# apu.net
KiCad netlist of a schematic drawn in Altium Designer
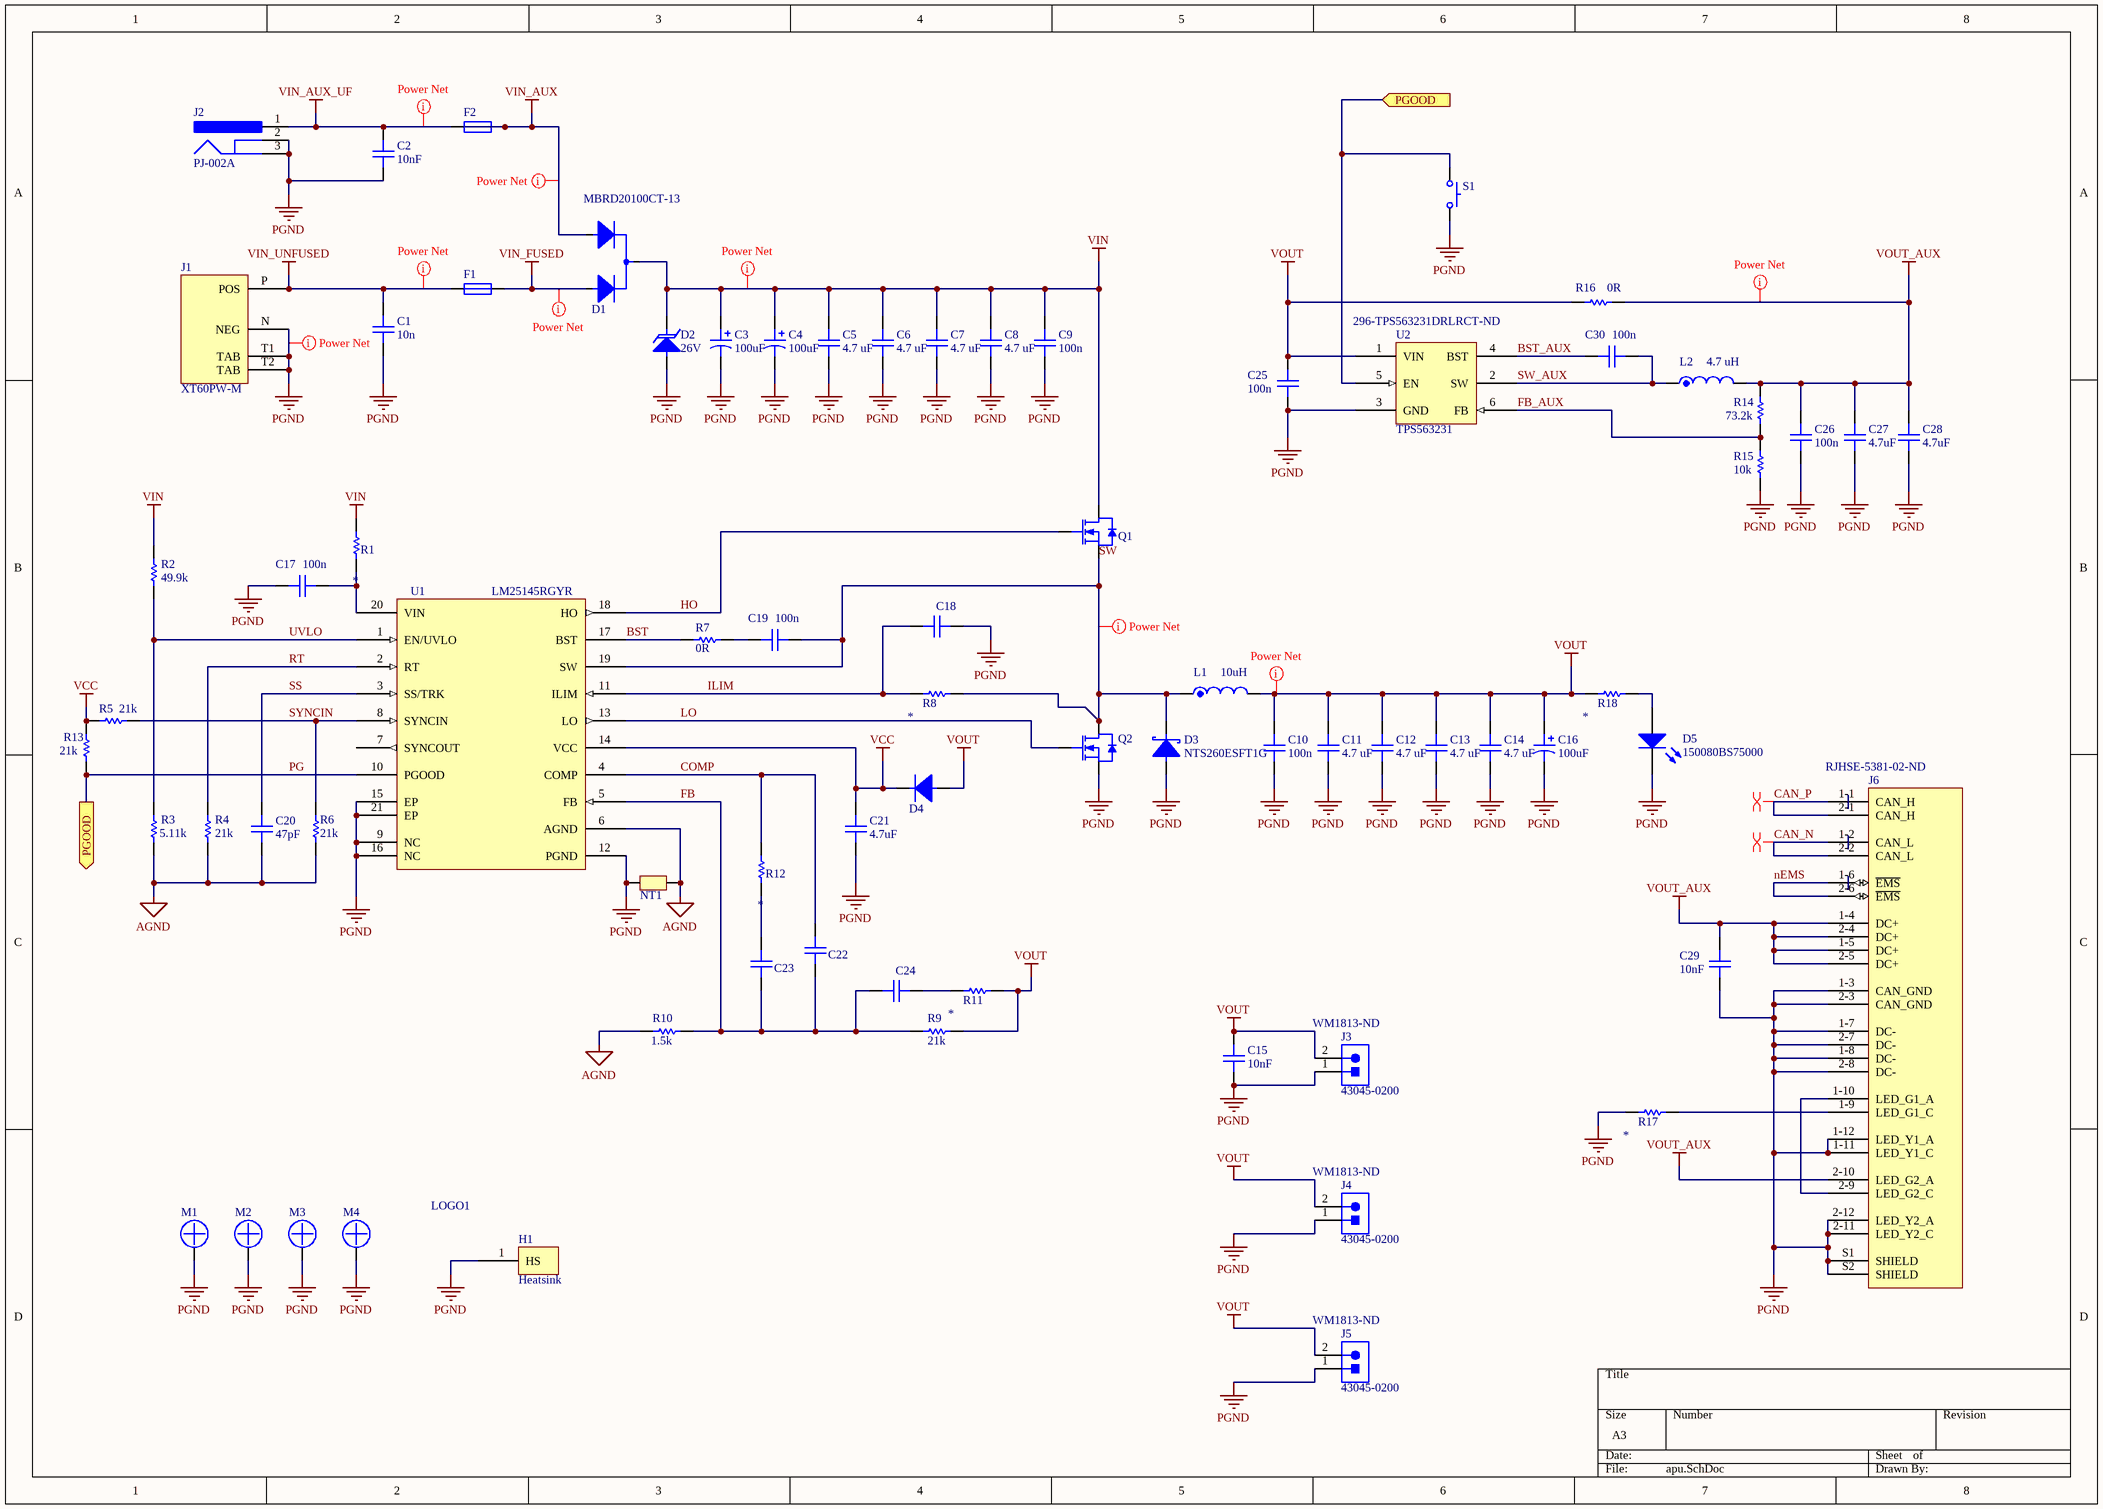
[diagram p0: apu.SchDoc]

(export (version "E")
  (design (tool "Eeschema 10.0.6"))
  (components
    (comp (ref "C1")
      (value "C")
      (footprint "C0603N")
      (description "CAP CER, 0.01UF, 50V, X7R, +/-20%, 0603")
      (fields (field (name "CAPACITANCE") "10n") (field (name "VOLTAGE") "50V"))
      (libsource (lib "libysk") (part "C"))
    )
    (comp (ref "C2")
      (value "C")
      (footprint "C0603N")
      (description "CAP CER, 0.01UF, 50V, X7R, +/-20%, 0603")
      (fields (field (name "CAPACITANCE") "10nF") (field (name "VOLTAGE") "50V"))
      (libsource (lib "libysk") (part "C"))
    )
    (comp (ref "C3")
      (value "UHE1H101MPD")
      (footprint "CPOL_8x11_5_THRU")
      (description "CAP ALUM 100UF 20% 50V RADIAL")
      (fields
        (field (name "CAPACITANCE") "100uF")
        (field (name "TOLERANCE") "20%")
        (field (name "VOLTAGE") "50V")
      )
      (libsource (lib "libysk") (part "CPOL"))
    )
    (comp (ref "C4")
      (value "UHE1H101MPD")
      (footprint "CPOL_8x11_5_THRU")
      (description "CAP ALUM 100UF 20% 50V RADIAL")
      (fields
        (field (name "CAPACITANCE") "100uF")
        (field (name "TOLERANCE") "20%")
        (field (name "VOLTAGE") "50V")
      )
      (libsource (lib "libysk") (part "CPOL"))
    )
    (comp (ref "C5")
      (value "UMK325B7475MM-P")
      (footprint "C1210N")
      (description "CAP CER 4.7UF 50V X7R 1210")
      (fields (field (name "CAPACITANCE") "4.7 uF") (field (name "VOLTAGE") "50 V"))
      (libsource (lib "libysk") (part "C"))
    )
    (comp (ref "C6")
      (value "UMK325B7475MM-P")
      (footprint "C1210N")
      (description "CAP CER 4.7UF 50V X7R 1210")
      (fields (field (name "CAPACITANCE") "4.7 uF") (field (name "VOLTAGE") "50 V"))
      (libsource (lib "libysk") (part "C"))
    )
    (comp (ref "C7")
      (value "UMK325B7475MM-P")
      (footprint "C1210N")
      (description "CAP CER 4.7UF 50V X7R 1210")
      (fields (field (name "CAPACITANCE") "4.7 uF") (field (name "VOLTAGE") "50 V"))
      (libsource (lib "libysk") (part "C"))
    )
    (comp (ref "C8")
      (value "UMK325B7475MM-P")
      (footprint "C1210N")
      (description "CAP CER 4.7UF 50V X7R 1210")
      (fields (field (name "CAPACITANCE") "4.7 uF") (field (name "VOLTAGE") "50 V"))
      (libsource (lib "libysk") (part "C"))
    )
    (comp (ref "C9")
      (value "C")
      (footprint "C0603N")
      (description "CAP CER, 0.1UF, 50V, X7R, +/-20%, 0603")
      (fields (field (name "VOLTAGE") "50 V") (field (name "DISPLAYVALUE") "100n"))
      (libsource (lib "libysk") (part "C"))
    )
    (comp (ref "C10")
      (value "C")
      (footprint "C0603N")
      (description "CAP CER, 0.1UF, 50V, X7R, +/-20%, 0603")
      (fields (field (name "VOLTAGE") "50 V") (field (name "DISPLAYVALUE") "100n"))
      (libsource (lib "libysk") (part "C"))
    )
    (comp (ref "C11")
      (value "UMK325B7475MM-P")
      (footprint "C1210N")
      (description "CAP CER 4.7UF 50V X7R 1210")
      (fields (field (name "CAPACITANCE") "4.7 uF") (field (name "VOLTAGE") "50 V"))
      (libsource (lib "libysk") (part "C"))
    )
    (comp (ref "C12")
      (value "UMK325B7475MM-P")
      (footprint "C1210N")
      (description "CAP CER 4.7UF 50V X7R 1210")
      (fields (field (name "CAPACITANCE") "4.7 uF") (field (name "VOLTAGE") "50 V"))
      (libsource (lib "libysk") (part "C"))
    )
    (comp (ref "C13")
      (value "UMK325B7475MM-P")
      (footprint "C1210N")
      (description "CAP CER 4.7UF 50V X7R 1210")
      (fields (field (name "CAPACITANCE") "4.7 uF") (field (name "VOLTAGE") "50 V"))
      (libsource (lib "libysk") (part "C"))
    )
    (comp (ref "C14")
      (value "UMK325B7475MM-P")
      (footprint "C1210N")
      (description "CAP CER 4.7UF 50V X7R 1210")
      (fields (field (name "CAPACITANCE") "4.7 uF") (field (name "VOLTAGE") "50 V"))
      (libsource (lib "libysk") (part "C"))
    )
    (comp (ref "C15")
      (value "C")
      (footprint "C0603N")
      (description "CAP CER, 0.01UF, 50V, X7R, +/-20%, 0603")
      (fields (field (name "CAPACITANCE") "10nF") (field (name "VOLTAGE") "50V"))
      (libsource (lib "libysk") (part "C"))
    )
    (comp (ref "C16")
      (value "UHE1H101MPD")
      (footprint "CPOL_8x11_5_THRU")
      (description "CAP ALUM 100UF 20% 50V RADIAL")
      (fields
        (field (name "CAPACITANCE") "100uF")
        (field (name "TOLERANCE") "20%")
        (field (name "VOLTAGE") "50V")
      )
      (libsource (lib "libysk") (part "CPOL"))
    )
    (comp (ref "C17")
      (value "C")
      (footprint "C0603N")
      (description "CAP CER, 0.1UF, 50V, X7R, +/-20%, 0603")
      (fields (field (name "VOLTAGE") "50 V") (field (name "DISPLAYVALUE") "100n"))
      (libsource (lib "libysk") (part "C"))
    )
    (comp (ref "C18") (value "~") (footprint "C0603N") (libsource (lib "libysk") (part "C")))
    (comp (ref "C19")
      (value "C")
      (footprint "C0603N")
      (description "CAP CER, 0.1UF, 50V, X7R, +/-20%, 0603")
      (fields (field (name "DISPLAYVALUE") "100n"))
      (libsource (lib "libysk") (part "C"))
    )
    (comp (ref "C20")
      (value "885012006055")
      (footprint "C0603N")
      (description "CAP CER 47PF 50V C0G/NP0 0603")
      (fields (field (name "TOLERANCE") "5%") (field (name "CAPACITANCE") "47pF"))
      (libsource (lib "libysk") (part "C"))
    )
    (comp (ref "C21")
      (value "TMK212ABJ475KG-T")
      (footprint "C0805N")
      (description "Prices include import duty and tax. CAPACITOR, MLCC , 0805, 25V , X5R, 4.7UF;")
      (fields (field (name "CAPACITANCE") "4.7uF") (field (name "TOLERANCE") "10%"))
      (libsource (lib "libysk") (part "C"))
    )
    (comp (ref "C22") (value "~") (footprint "C0603N") (libsource (lib "libysk") (part "C")))
    (comp (ref "C23") (value "~") (footprint "C0603N") (libsource (lib "libysk") (part "C")))
    (comp (ref "C24") (value "~") (footprint "C0603N") (libsource (lib "libysk") (part "C")))
    (comp (ref "C25")
      (value "C")
      (footprint "C0603N")
      (description "CAP CER, 0.1UF, 50V, X7R, +/-20%, 0603")
      (fields (field (name "VOLTAGE") "50 V") (field (name "DISPLAYVALUE") "100n"))
      (libsource (lib "libysk") (part "C"))
    )
    (comp (ref "C26")
      (value "C")
      (footprint "C0603N")
      (description "CAP CER, 0.1UF, 50V, X7R, +/-20%, 0603")
      (fields (field (name "VOLTAGE") "50 V") (field (name "DISPLAYVALUE") "100n"))
      (libsource (lib "libysk") (part "C"))
    )
    (comp (ref "C27")
      (value "TMK212ABJ475KG-T")
      (footprint "C0805N")
      (description "Prices include import duty and tax. CAPACITOR, MLCC , 0805, 25V , X5R, 4.7UF;")
      (fields (field (name "CAPACITANCE") "4.7uF") (field (name "TOLERANCE") "10%"))
      (libsource (lib "libysk") (part "C"))
    )
    (comp (ref "C28")
      (value "TMK212ABJ475KG-T")
      (footprint "C0805N")
      (description "Prices include import duty and tax. CAPACITOR, MLCC , 0805, 25V , X5R, 4.7UF;")
      (fields (field (name "CAPACITANCE") "4.7uF") (field (name "TOLERANCE") "10%"))
      (libsource (lib "libysk") (part "C"))
    )
    (comp (ref "C29")
      (value "C")
      (footprint "C0603N")
      (description "CAP CER, 0.01UF, 50V, X7R, +/-20%, 0603")
      (fields (field (name "CAPACITANCE") "10nF") (field (name "VOLTAGE") "50V"))
      (libsource (lib "libysk") (part "C"))
    )
    (comp (ref "C30")
      (value "C")
      (footprint "C0603N")
      (description "CAP CER, 0.1UF, 50V, X7R, +/-20%, 0603")
      (fields (field (name "VOLTAGE") "50 V") (field (name "DISPLAYVALUE") "100n"))
      (libsource (lib "libysk") (part "C"))
    )
    (comp (ref "D1")
      (value "MBRD20100CT-13")
      (footprint "DPAK_JEDEC_N")
      (description "DIODE SCHOTTKY 100V 10A TO252")
      (fields
        (field (name "MANUFACTURER") "Diodes")
        (field (name "MANUFACTURER PART NUMBER") "MBRD20100CT-13")
      )
      (libsource (lib "libysk") (part "D_CC"))
    )
    (comp (ref "D2")
      (value "SMBJ26A-E3/52")
      (footprint "SMB")
      (description "Diode TVS Single Uni-Dir 26V 600W 2-Pin SMB T/R")
      (fields (field (name "REVERSE STANDOFF VOLTAGE") "26V"))
      (libsource (lib "libysk") (part "TVS"))
    )
    (comp (ref "D3")
      (value "NTS260ESFT1G")
      (footprint "SOD-123FLN")
      (description "DIODE SCHOTTKY 60V 2A SOD123FL")
      (fields (field (name "MANUFACTURER PART NUMBER 1") "NTS260ESFT1G"))
      (libsource (lib "libysk") (part "SBD"))
    )
    (comp (ref "D4") (value "~") (footprint "SOD323FLN") (libsource (lib "libysk") (part "D")))
    (comp (ref "D5")
      (value "150080BS75000")
      (footprint "0805_A")
      (description "SMD mono-color Chip LED, WL-SMCW, Blue")
      (fields (field (name "MANUFACTURER") "Wuerth Elektronik"))
      (libsource (lib "Altium Content Vault") (part "WE-LED_K1A2-2"))
    )
    (comp (ref "F1") (value "FUSE") (footprint "LITTELFUSE_154") (libsource (lib "libysk") (part "FUSE")))
    (comp (ref "F2") (value "FUSE") (footprint "LITTELFUSE_154") (libsource (lib "libysk") (part "FUSE")))
    (comp (ref "H1") (value "Heatsink") (footprint "HS_2510") (libsource (lib "libysk") (part "Heatsink")))
    (comp (ref "J1")
      (value "XT60PW-M")
      (footprint "XT60PW-M")
      (description "XT60, Male, THT, R/A")
      (libsource (lib "libysk") (part "XT60PW-M"))
    )
    (comp (ref "J2")
      (value "PJ-002A")
      (footprint "CUI-PJ-002A_V")
      (fields (field (name "MANUFACTURER") "CUIInc.") (field (name "MANUFACTURER PART NUMBER") "PJ-002B"))
      (libsource (lib "Altium Content Vault") (part "JACK-2CD3-RN"))
    )
    (comp (ref "J3")
      (value "43045-0200")
      (footprint "43045-020X")
      (description "Header 2 Row Right-Angle Snap-In Lock 2Pin Tin Plate SMT/Glow Wire Compatible")
      (fields (field (name "SUPPLIER PART NUMBER 1") "WM1813-ND"))
      (libsource (lib "libysk") (part "43045-020X"))
    )
    (comp (ref "J4")
      (value "43045-0200")
      (footprint "43045-020X")
      (description "Header 2 Row Right-Angle Snap-In Lock 2Pin Tin Plate SMT/Glow Wire Compatible")
      (fields (field (name "SUPPLIER PART NUMBER 1") "WM1813-ND"))
      (libsource (lib "libysk") (part "43045-020X"))
    )
    (comp (ref "J5")
      (value "43045-0200")
      (footprint "43045-020X")
      (description "Header 2 Row Right-Angle Snap-In Lock 2Pin Tin Plate SMT/Glow Wire Compatible")
      (fields (field (name "SUPPLIER PART NUMBER 1") "WM1813-ND"))
      (libsource (lib "libysk") (part "43045-020X"))
    )
    (comp (ref "J6")
      (value "RJHSE-5381-02")
      (footprint "RJHSE-X38X-02")
      (description "CONN MOD JACK 8P8C R/A SHIELDED")
      (fields (field (name "SUPPLIER PART NUMBER 1") "RJHSE-5381-02-ND"))
      (libsource (lib "libysk") (part "RJHSE-X381-02"))
    )
    (comp (ref "L1")
      (value "SRP1265A-100M")
      (footprint "SRP1265A")
      (description "FIXED IND 10UH 10A 16.5 MOHM SMD")
      (fields (field (name "TOLERANCE") "20%") (field (name "INDUCTANCE") "10uH"))
      (libsource (lib "libysk") (part "L"))
    )
    (comp (ref "L2")
      (value "~")
      (footprint "VLS5045EX_TDK")
      (fields (field (name "CAPACITANCE") "4.7 uH"))
      (libsource (lib "libysk") (part "L"))
    )
    (comp (ref "LOGO1")
      (value "LOGO")
      (footprint "LOGO_designed_by_ysk")
      (libsource (lib "libysk") (part "LOGO"))
    )
    (comp (ref "M1")
      (value "Mounting_Screw")
      (footprint "MOUNT_HOLE_3.2")
      (libsource (lib "libysk") (part "Mounting_Screw"))
    )
    (comp (ref "M2")
      (value "Mounting_Screw")
      (footprint "MOUNT_HOLE_3.2")
      (libsource (lib "libysk") (part "Mounting_Screw"))
    )
    (comp (ref "M3")
      (value "Mounting_Screw")
      (footprint "MOUNT_HOLE_3.2")
      (libsource (lib "libysk") (part "Mounting_Screw"))
    )
    (comp (ref "M4")
      (value "Mounting_Screw")
      (footprint "MOUNT_HOLE_3.2")
      (libsource (lib "libysk") (part "Mounting_Screw"))
    )
    (comp (ref "NT1") (value "Net tie") (footprint "NET_TIE_0_2") (libsource (lib "libysk") (part "NET TIE")))
    (comp (ref "Q1")
      (value "MOSFET-N")
      (footprint "DFN-5 (SO-8FL)")
      (libsource (lib "libysk") (part "MOSFET-N"))
    )
    (comp (ref "Q2")
      (value "MOSFET-N")
      (footprint "DFN-5 (SO-8FL)")
      (libsource (lib "libysk") (part "MOSFET-N"))
    )
    (comp (ref "R1")
      (value "R")
      (footprint "R0603N")
      (description "RES SMD, 10KOHM, 1%, 0.1W, 0603")
      (fields (field (name "MANUFACTURER") "Any") (field (name "RESISTANCE") "*"))
      (libsource (lib "libysk") (part "R"))
    )
    (comp (ref "R2")
      (value "R")
      (footprint "R0603N")
      (description "RES SMD, 49.9KOHM, 1%, 0.1W, 0603")
      (fields (field (name "MANUFACTURER") "Any") (field (name "RESISTANCE") "49.9k"))
      (libsource (lib "libysk") (part "R"))
    )
    (comp (ref "R3")
      (value "R")
      (footprint "R0603N")
      (description "RES SMD, 5.11KOHM, 1%, 0.1W, 0603")
      (fields (field (name "MANUFACTURER") "Any") (field (name "RESISTANCE") "5.11k"))
      (libsource (lib "libysk") (part "R"))
    )
    (comp (ref "R4")
      (value "R")
      (footprint "R0603N")
      (description "RES SMD, 10KOHM, 1%, 0.1W, 0603")
      (fields (field (name "RESISTANCE") "21k") (field (name "MANUFACTURER") "Any"))
      (libsource (lib "libysk") (part "R"))
    )
    (comp (ref "R5")
      (value "R")
      (footprint "R0603N")
      (description "RES SMD, 10KOHM, 1%, 0.1W, 0603")
      (fields (field (name "MANUFACTURER") "Any") (field (name "RESISTANCE") "21k"))
      (libsource (lib "libysk") (part "R"))
    )
    (comp (ref "R6")
      (value "R")
      (footprint "R0603N")
      (description "RES SMD, 10KOHM, 1%, 0.1W, 0603")
      (fields (field (name "MANUFACTURER") "Any") (field (name "RESISTANCE") "21k"))
      (libsource (lib "libysk") (part "R"))
    )
    (comp (ref "R7")
      (value "R")
      (footprint "R0603N")
      (description "RES SMD, 10KOHM, 1%, 0.1W, 0603")
      (fields (field (name "RESISTANCE") "0R") (field (name "MANUFACTURER") "Any"))
      (libsource (lib "libysk") (part "R"))
    )
    (comp (ref "R8")
      (value "R")
      (footprint "R0603N")
      (description "RES SMD, 10KOHM, 1%, 0.1W, 0603")
      (fields (field (name "MANUFACTURER") "Any") (field (name "RESISTANCE") "*"))
      (libsource (lib "libysk") (part "R"))
    )
    (comp (ref "R9")
      (value "R")
      (footprint "R0603N")
      (description "RES SMD, 10KOHM, 1%, 0.1W, 0603")
      (fields (field (name "RESISTANCE") "21k") (field (name "MANUFACTURER") "Any"))
      (libsource (lib "libysk") (part "R"))
    )
    (comp (ref "R10")
      (value "R")
      (footprint "R0603N")
      (description "RES SMD, 10KOHM, 1%, 0.1W, 0603")
      (fields (field (name "RESISTANCE") "1.5k") (field (name "MANUFACTURER") "Any"))
      (libsource (lib "libysk") (part "R"))
    )
    (comp (ref "R11")
      (value "R")
      (footprint "R0603N")
      (description "RES SMD, 10KOHM, 1%, 0.1W, 0603")
      (fields (field (name "MANUFACTURER") "Any") (field (name "RESISTANCE") "*"))
      (libsource (lib "libysk") (part "R"))
    )
    (comp (ref "R12")
      (value "R")
      (footprint "R0603N")
      (description "RES SMD, 10KOHM, 1%, 0.1W, 0603")
      (fields (field (name "MANUFACTURER") "Any") (field (name "RESISTANCE") "*"))
      (libsource (lib "libysk") (part "R"))
    )
    (comp (ref "R13")
      (value "R")
      (footprint "R0603N")
      (description "RES SMD, 10KOHM, 1%, 0.1W, 0603")
      (fields (field (name "MANUFACTURER") "Any") (field (name "RESISTANCE") "21k"))
      (libsource (lib "libysk") (part "R"))
    )
    (comp (ref "R14")
      (value "R")
      (footprint "R0603N")
      (description "RES SMD, 10KOHM, 1%, 0.1W, 0603")
      (fields (field (name "RESISTANCE") "73.2k") (field (name "MANUFACTURER") "Any"))
      (libsource (lib "libysk") (part "R"))
    )
    (comp (ref "R15")
      (value "R")
      (footprint "R0603N")
      (description "RES SMD, 10KOHM, 1%, 0.1W, 0603")
      (fields (field (name "RESISTANCE") "10k") (field (name "MANUFACTURER") "Any"))
      (libsource (lib "libysk") (part "R"))
    )
    (comp (ref "R16")
      (value "R")
      (footprint "R1206N")
      (fields (field (name "RESISTANCE") "0R"))
      (libsource (lib "libysk") (part "R"))
    )
    (comp (ref "R17")
      (value "R")
      (footprint "R0603N")
      (description "RES SMD, 10KOHM, 1%, 0.1W, 0603")
      (fields (field (name "MANUFACTURER") "Any") (field (name "RESISTANCE") "*"))
      (libsource (lib "libysk") (part "R"))
    )
    (comp (ref "R18")
      (value "R")
      (footprint "R0603N")
      (description "RES SMD, 10KOHM, 1%, 0.1W, 0603")
      (fields (field (name "MANUFACTURER") "Any") (field (name "RESISTANCE") "*"))
      (libsource (lib "libysk") (part "R"))
    )
    (comp (ref "S1")
      (value "SW")
      (footprint "SW_TACTILE_3x6")
      (description "SW TACTILE")
      (libsource (lib "libysk_switches") (part "TactileSwitch"))
    )
    (comp (ref "U1")
      (value "~")
      (footprint "RGY0020B_TI_N")
      (description "6-V to 42-V Synchronous Buck DC-DC Controller With Wide Duty Cycle Range")
      (fields (field (name "MANUFACTURER PART NUMBER 1") "LM25145RGYR"))
      (libsource (lib "libysk") (part "LM25145"))
    )
    (comp (ref "U2")
      (value "TPS563231")
      (footprint "DRL0006A_TI_N")
      (description "4.5-V to 17-V input, 3-A synchronous step-down voltage regulator 6-SOT-5X3 -40 to 125")
      (fields
        (field (name "SUPPLIER PART NUMBER 1") "296-TPS563231DRLRCT-ND")
        (field (name "MANUFACTURER") "Texas Instruments")
        (field (name "MANUFACTURER PART NUMBER") "TPS563231DRLR")
      )
      (libsource (lib "libysk") (part "TPS563231"))
    )
  )
  (nets
    (net (code "1") (name "/BST") (class "Default")
      (node (ref "R7") (pin "1") (pinfunction "1_1") (pintype "passive"))
      (node (ref "U1") (pin "17") (pinfunction "BST_17") (pintype "passive"))
    )
    (net (code "2") (name "/BST_AUX") (class "Default")
      (node (ref "C30") (pin "1") (pinfunction "1_1") (pintype "passive"))
      (node (ref "U2") (pin "4") (pinfunction "BST_4") (pintype "passive"))
    )
    (net (code "3") (name "/CAN_N") (class "Default")
      (node (ref "J6") (pin "1-2") (pinfunction "CAN_L_1-2") (pintype "passive"))
      (node (ref "J6") (pin "2-2") (pinfunction "CAN_L_2-2") (pintype "passive"))
    )
    (net (code "4") (name "/CAN_P") (class "Default")
      (node (ref "J6") (pin "1-1") (pinfunction "CAN_H_1-1") (pintype "passive"))
      (node (ref "J6") (pin "2-1") (pinfunction "CAN_H_2-1") (pintype "passive"))
    )
    (net (code "5") (name "/COMP") (class "Default")
      (node (ref "C22") (pin "1") (pinfunction "1_1") (pintype "passive"))
      (node (ref "R12") (pin "2") (pinfunction "2_2") (pintype "passive"))
      (node (ref "U1") (pin "4") (pinfunction "COMP_4") (pintype "passive"))
    )
    (net (code "6") (name "/FB") (class "Default")
      (node (ref "C22") (pin "2") (pinfunction "2_2") (pintype "passive"))
      (node (ref "C23") (pin "2") (pinfunction "2_2") (pintype "passive"))
      (node (ref "C24") (pin "2") (pinfunction "2_2") (pintype "passive"))
      (node (ref "R10") (pin "2") (pinfunction "2_2") (pintype "passive"))
      (node (ref "R9") (pin "1") (pinfunction "1_1") (pintype "passive"))
      (node (ref "U1") (pin "5") (pinfunction "FB_5") (pintype "input"))
    )
    (net (code "7") (name "/FB_AUX") (class "Default")
      (node (ref "R14") (pin "1") (pinfunction "1_1") (pintype "passive"))
      (node (ref "R15") (pin "2") (pinfunction "2_2") (pintype "passive"))
      (node (ref "U2") (pin "6") (pinfunction "FB_6") (pintype "input"))
    )
    (net (code "8") (name "/HO") (class "Default")
      (node (ref "Q1") (pin "G") (pinfunction "G_G") (pintype "passive"))
      (node (ref "U1") (pin "18") (pinfunction "HO_18") (pintype "output"))
    )
    (net (code "9") (name "/ILIM") (class "Default")
      (node (ref "C18") (pin "2") (pinfunction "2_2") (pintype "passive"))
      (node (ref "R8") (pin "1") (pinfunction "1_1") (pintype "passive"))
      (node (ref "U1") (pin "11") (pinfunction "ILIM_11") (pintype "input"))
    )
    (net (code "10") (name "/LO") (class "Default")
      (node (ref "Q2") (pin "G") (pinfunction "G_G") (pintype "passive"))
      (node (ref "U1") (pin "13") (pinfunction "LO_13") (pintype "output"))
    )
    (net (code "11") (name "/PG") (class "Default")
      (node (ref "R13") (pin "1") (pinfunction "1_1") (pintype "passive"))
      (node (ref "S1") (pin "1") (pinfunction "1_1") (pintype "passive"))
      (node (ref "U1") (pin "10") (pinfunction "PGOOD_10") (pintype "open_collector"))
      (node (ref "U2") (pin "5") (pinfunction "EN_5") (pintype "input"))
    )
    (net (code "12") (name "/RT") (class "Default")
      (node (ref "R4") (pin "2") (pinfunction "2_2") (pintype "passive"))
      (node (ref "U1") (pin "2") (pinfunction "RT_2") (pintype "input"))
    )
    (net (code "13") (name "/SS") (class "Default")
      (node (ref "C20") (pin "2") (pinfunction "2_2") (pintype "passive"))
      (node (ref "U1") (pin "3") (pinfunction "SS/TRK_3") (pintype "input"))
    )
    (net (code "14") (name "/SW") (class "Default")
      (node (ref "C19") (pin "1") (pinfunction "1_1") (pintype "passive"))
      (node (ref "D3") (pin "1") (pinfunction "C_1") (pintype "passive"))
      (node (ref "L1") (pin "1") (pinfunction "1_1") (pintype "passive"))
      (node (ref "Q1") (pin "S") (pinfunction "S_S") (pintype "passive"))
      (node (ref "Q2") (pin "D") (pinfunction "D_D") (pintype "passive"))
      (node (ref "R8") (pin "2") (pinfunction "2_2") (pintype "passive"))
      (node (ref "U1") (pin "19") (pinfunction "SW_19") (pintype "passive"))
    )
    (net (code "15") (name "/SW_AUX") (class "Default")
      (node (ref "C30") (pin "2") (pinfunction "2_2") (pintype "passive"))
      (node (ref "L2") (pin "1") (pinfunction "1_1") (pintype "passive"))
      (node (ref "U2") (pin "2") (pinfunction "SW_2") (pintype "passive"))
    )
    (net (code "16") (name "/SYNCIN") (class "Default")
      (node (ref "R5") (pin "1") (pinfunction "1_1") (pintype "passive"))
      (node (ref "R6") (pin "1") (pinfunction "1_1") (pintype "passive"))
      (node (ref "U1") (pin "8") (pinfunction "SYNCIN_8") (pintype "input"))
    )
    (net (code "17") (name "/UVLO") (class "Default")
      (node (ref "R2") (pin "1") (pinfunction "1_1") (pintype "passive"))
      (node (ref "R3") (pin "2") (pinfunction "2_2") (pintype "passive"))
      (node (ref "U1") (pin "1") (pinfunction "EN/UVLO_1") (pintype "input"))
    )
    (net (code "18") (name "/nEMS") (class "Default")
      (node (ref "J6") (pin "1-6") (pinfunction "~{EMS}_1-6") (pintype "bidirectional"))
      (node (ref "J6") (pin "2-6") (pinfunction "~{EMS}_2-6") (pintype "bidirectional"))
    )
    (net (code "19") (name "AGND") (class "Default")
      (node (ref "C20") (pin "1") (pinfunction "1_1") (pintype "passive"))
      (node (ref "NT1") (pin "2") (pinfunction "2_2") (pintype "passive"))
      (node (ref "R10") (pin "1") (pinfunction "1_1") (pintype "passive"))
      (node (ref "R3") (pin "1") (pinfunction "1_1") (pintype "passive"))
      (node (ref "R4") (pin "1") (pinfunction "1_1") (pintype "passive"))
      (node (ref "R6") (pin "2") (pinfunction "2_2") (pintype "passive"))
      (node (ref "U1") (pin "6") (pinfunction "AGND_6") (pintype "power_in"))
    )
    (net (code "20") (name "Net-(C19-Pad2)") (class "Default")
      (node (ref "C19") (pin "2") (pinfunction "2_2") (pintype "passive"))
      (node (ref "R7") (pin "2") (pinfunction "2_2") (pintype "passive"))
    )
    (net (code "21") (name "Net-(C23-Pad1)") (class "Default")
      (node (ref "C23") (pin "1") (pinfunction "1_1") (pintype "passive"))
      (node (ref "R12") (pin "1") (pinfunction "1_1") (pintype "passive"))
    )
    (net (code "22") (name "Net-(C24-Pad1)") (class "Default")
      (node (ref "C24") (pin "1") (pinfunction "1_1") (pintype "passive"))
      (node (ref "R11") (pin "1") (pinfunction "1_1") (pintype "passive"))
    )
    (net (code "23") (name "Net-(D5-A)") (class "Default")
      (node (ref "D5") (pin "2") (pinfunction "A_2") (pintype "passive"))
      (node (ref "R18") (pin "1") (pinfunction "1_1") (pintype "passive"))
    )
    (net (code "24") (name "Net-(J6-LED_G1_A)") (class "Default")
      (node (ref "J6") (pin "1-10") (pinfunction "LED_G1_A_1-10") (pintype "passive"))
      (node (ref "J6") (pin "2-9") (pinfunction "LED_G2_C_2-9") (pintype "passive"))
    )
    (net (code "25") (name "Net-(J6-LED_G1_C)") (class "Default")
      (node (ref "J6") (pin "1-9") (pinfunction "LED_G1_C_1-9") (pintype "passive"))
      (node (ref "R17") (pin "1") (pinfunction "1_1") (pintype "passive"))
    )
    (net (code "26") (name "Net-(U1-VIN)") (class "Default")
      (node (ref "C17") (pin "1") (pinfunction "1_1") (pintype "passive"))
      (node (ref "R1") (pin "2") (pinfunction "2_2") (pintype "passive"))
      (node (ref "U1") (pin "20") (pinfunction "VIN_20") (pintype "power_in"))
    )
    (net (code "27") (name "PGND") (class "Default")
      (node (ref "C1") (pin "2") (pinfunction "2_2") (pintype "passive"))
      (node (ref "C10") (pin "2") (pinfunction "2_2") (pintype "passive"))
      (node (ref "C11") (pin "1") (pinfunction "1_1") (pintype "passive"))
      (node (ref "C12") (pin "1") (pinfunction "1_1") (pintype "passive"))
      (node (ref "C13") (pin "1") (pinfunction "1_1") (pintype "passive"))
      (node (ref "C14") (pin "1") (pinfunction "1_1") (pintype "passive"))
      (node (ref "C15") (pin "2") (pinfunction "2_2") (pintype "passive"))
      (node (ref "C16") (pin "2") (pinfunction "2_2") (pintype "passive"))
      (node (ref "C17") (pin "2") (pinfunction "2_2") (pintype "passive"))
      (node (ref "C18") (pin "1") (pinfunction "1_1") (pintype "passive"))
      (node (ref "C2") (pin "2") (pinfunction "2_2") (pintype "passive"))
      (node (ref "C21") (pin "1") (pinfunction "1_1") (pintype "passive"))
      (node (ref "C25") (pin "2") (pinfunction "2_2") (pintype "passive"))
      (node (ref "C26") (pin "2") (pinfunction "2_2") (pintype "passive"))
      (node (ref "C27") (pin "1") (pinfunction "1_1") (pintype "passive"))
      (node (ref "C28") (pin "1") (pinfunction "1_1") (pintype "passive"))
      (node (ref "C29") (pin "2") (pinfunction "2_2") (pintype "passive"))
      (node (ref "C3") (pin "2") (pinfunction "2_2") (pintype "passive"))
      (node (ref "C4") (pin "2") (pinfunction "2_2") (pintype "passive"))
      (node (ref "C5") (pin "1") (pinfunction "1_1") (pintype "passive"))
      (node (ref "C6") (pin "1") (pinfunction "1_1") (pintype "passive"))
      (node (ref "C7") (pin "1") (pinfunction "1_1") (pintype "passive"))
      (node (ref "C8") (pin "1") (pinfunction "1_1") (pintype "passive"))
      (node (ref "C9") (pin "2") (pinfunction "2_2") (pintype "passive"))
      (node (ref "D2") (pin "2") (pinfunction "A_2") (pintype "passive"))
      (node (ref "D3") (pin "2") (pinfunction "A_2") (pintype "passive"))
      (node (ref "D5") (pin "1") (pinfunction "K_1") (pintype "passive"))
      (node (ref "H1") (pin "1") (pinfunction "HS_1") (pintype "passive"))
      (node (ref "J1") (pin "N") (pinfunction "NEG_N") (pintype "passive"))
      (node (ref "J1") (pin "T1") (pinfunction "TAB_T1") (pintype "passive"))
      (node (ref "J1") (pin "T2") (pinfunction "TAB_T2") (pintype "passive"))
      (node (ref "J2") (pin "2") (pinfunction "2_2") (pintype "passive"))
      (node (ref "J2") (pin "3") (pinfunction "3_3") (pintype "passive"))
      (node (ref "J3") (pin "1") (pinfunction "1_1") (pintype "passive"))
      (node (ref "J4") (pin "1") (pinfunction "1_1") (pintype "passive"))
      (node (ref "J5") (pin "1") (pinfunction "1_1") (pintype "passive"))
      (node (ref "J6") (pin "1-11") (pinfunction "LED_Y1_C_1-11") (pintype "passive"))
      (node (ref "J6") (pin "1-12") (pinfunction "LED_Y1_A_1-12") (pintype "passive"))
      (node (ref "J6") (pin "1-3") (pinfunction "CAN_GND_1-3") (pintype "passive"))
      (node (ref "J6") (pin "1-7") (pinfunction "DC-_1-7") (pintype "passive"))
      (node (ref "J6") (pin "1-8") (pinfunction "DC-_1-8") (pintype "passive"))
      (node (ref "J6") (pin "2-11") (pinfunction "LED_Y2_C_2-11") (pintype "passive"))
      (node (ref "J6") (pin "2-12") (pinfunction "LED_Y2_A_2-12") (pintype "passive"))
      (node (ref "J6") (pin "2-3") (pinfunction "CAN_GND_2-3") (pintype "passive"))
      (node (ref "J6") (pin "2-7") (pinfunction "DC-_2-7") (pintype "passive"))
      (node (ref "J6") (pin "2-8") (pinfunction "DC-_2-8") (pintype "passive"))
      (node (ref "J6") (pin "S1") (pinfunction "SHIELD_S1") (pintype "passive"))
      (node (ref "J6") (pin "S2") (pinfunction "SHIELD_S2") (pintype "passive"))
      (node (ref "M1") (pin "1") (pinfunction "1_1") (pintype "passive"))
      (node (ref "M2") (pin "1") (pinfunction "1_1") (pintype "passive"))
      (node (ref "M3") (pin "1") (pinfunction "1_1") (pintype "passive"))
      (node (ref "M4") (pin "1") (pinfunction "1_1") (pintype "passive"))
      (node (ref "NT1") (pin "1") (pinfunction "1_1") (pintype "passive"))
      (node (ref "Q2") (pin "S") (pinfunction "S_S") (pintype "passive"))
      (node (ref "R15") (pin "1") (pinfunction "1_1") (pintype "passive"))
      (node (ref "R17") (pin "2") (pinfunction "2_2") (pintype "passive"))
      (node (ref "S1") (pin "1") (pinfunction "1_1") (pintype "passive"))
      (node (ref "U1") (pin "12") (pinfunction "PGND_12") (pintype "power_in"))
      (node (ref "U1") (pin "15") (pinfunction "EP_15") (pintype "passive"))
      (node (ref "U1") (pin "16") (pinfunction "NC_16") (pintype "passive"))
      (node (ref "U1") (pin "21") (pinfunction "EP_21") (pintype "passive"))
      (node (ref "U1") (pin "9") (pinfunction "NC_9") (pintype "passive"))
      (node (ref "U2") (pin "3") (pinfunction "GND_3") (pintype "power_in"))
    )
    (net (code "28") (name "VCC") (class "Default")
      (node (ref "C21") (pin "2") (pinfunction "2_2") (pintype "passive"))
      (node (ref "D4") (pin "1") (pinfunction "C_1") (pintype "passive"))
      (node (ref "R13") (pin "2") (pinfunction "2_2") (pintype "passive"))
      (node (ref "R5") (pin "2") (pinfunction "2_2") (pintype "passive"))
      (node (ref "U1") (pin "14") (pinfunction "VCC_14") (pintype "passive"))
    )
    (net (code "29") (name "VIN") (class "Default")
      (node (ref "C3") (pin "1") (pinfunction "1_1") (pintype "passive"))
      (node (ref "C4") (pin "1") (pinfunction "1_1") (pintype "passive"))
      (node (ref "C5") (pin "2") (pinfunction "2_2") (pintype "passive"))
      (node (ref "C6") (pin "2") (pinfunction "2_2") (pintype "passive"))
      (node (ref "C7") (pin "2") (pinfunction "2_2") (pintype "passive"))
      (node (ref "C8") (pin "2") (pinfunction "2_2") (pintype "passive"))
      (node (ref "C9") (pin "1") (pinfunction "1_1") (pintype "passive"))
      (node (ref "D1") (pin "2") (pinfunction "C_2") (pintype "passive"))
      (node (ref "D2") (pin "1") (pinfunction "C_1") (pintype "passive"))
      (node (ref "Q1") (pin "D") (pinfunction "D_D") (pintype "passive"))
      (node (ref "R1") (pin "1") (pinfunction "1_1") (pintype "passive"))
      (node (ref "R2") (pin "2") (pinfunction "2_2") (pintype "passive"))
    )
    (net (code "30") (name "VIN_AUX") (class "Default")
      (node (ref "D1") (pin "3") (pinfunction "A2_3") (pintype "passive"))
      (node (ref "F2") (pin "2") (pinfunction "2_2") (pintype "passive"))
    )
    (net (code "31") (name "VIN_AUX_UF") (class "Default")
      (node (ref "C2") (pin "1") (pinfunction "1_1") (pintype "passive"))
      (node (ref "F2") (pin "1") (pinfunction "1_1") (pintype "passive"))
      (node (ref "J2") (pin "1") (pinfunction "1_1") (pintype "passive"))
    )
    (net (code "32") (name "VIN_FUSED") (class "Default")
      (node (ref "D1") (pin "1") (pinfunction "A1_1") (pintype "passive"))
      (node (ref "F1") (pin "2") (pinfunction "2_2") (pintype "passive"))
    )
    (net (code "33") (name "VIN_UNFUSED") (class "Default")
      (node (ref "C1") (pin "1") (pinfunction "1_1") (pintype "passive"))
      (node (ref "F1") (pin "1") (pinfunction "1_1") (pintype "passive"))
      (node (ref "J1") (pin "P") (pinfunction "POS_P") (pintype "passive"))
    )
    (net (code "34") (name "VOUT") (class "Default")
      (node (ref "C10") (pin "1") (pinfunction "1_1") (pintype "passive"))
      (node (ref "C11") (pin "2") (pinfunction "2_2") (pintype "passive"))
      (node (ref "C12") (pin "2") (pinfunction "2_2") (pintype "passive"))
      (node (ref "C13") (pin "2") (pinfunction "2_2") (pintype "passive"))
      (node (ref "C14") (pin "2") (pinfunction "2_2") (pintype "passive"))
      (node (ref "C15") (pin "1") (pinfunction "1_1") (pintype "passive"))
      (node (ref "C16") (pin "1") (pinfunction "1_1") (pintype "passive"))
      (node (ref "C25") (pin "1") (pinfunction "1_1") (pintype "passive"))
      (node (ref "D4") (pin "2") (pinfunction "A_2") (pintype "passive"))
      (node (ref "J3") (pin "2") (pinfunction "2_2") (pintype "passive"))
      (node (ref "J4") (pin "2") (pinfunction "2_2") (pintype "passive"))
      (node (ref "J5") (pin "2") (pinfunction "2_2") (pintype "passive"))
      (node (ref "L1") (pin "2") (pinfunction "2_2") (pintype "passive"))
      (node (ref "R11") (pin "2") (pinfunction "2_2") (pintype "passive"))
      (node (ref "R16") (pin "1") (pinfunction "1_1") (pintype "passive"))
      (node (ref "R18") (pin "2") (pinfunction "2_2") (pintype "passive"))
      (node (ref "R9") (pin "2") (pinfunction "2_2") (pintype "passive"))
      (node (ref "U2") (pin "1") (pinfunction "VIN_1") (pintype "power_in"))
    )
    (net (code "35") (name "VOUT_AUX") (class "Default")
      (node (ref "C26") (pin "1") (pinfunction "1_1") (pintype "passive"))
      (node (ref "C27") (pin "2") (pinfunction "2_2") (pintype "passive"))
      (node (ref "C28") (pin "2") (pinfunction "2_2") (pintype "passive"))
      (node (ref "C29") (pin "1") (pinfunction "1_1") (pintype "passive"))
      (node (ref "J6") (pin "1-4") (pinfunction "DC+_1-4") (pintype "passive"))
      (node (ref "J6") (pin "1-5") (pinfunction "DC+_1-5") (pintype "passive"))
      (node (ref "J6") (pin "2-10") (pinfunction "LED_G2_A_2-10") (pintype "passive"))
      (node (ref "J6") (pin "2-4") (pinfunction "DC+_2-4") (pintype "passive"))
      (node (ref "J6") (pin "2-5") (pinfunction "DC+_2-5") (pintype "passive"))
      (node (ref "L2") (pin "2") (pinfunction "2_2") (pintype "passive"))
      (node (ref "R14") (pin "2") (pinfunction "2_2") (pintype "passive"))
      (node (ref "R16") (pin "2") (pinfunction "2_2") (pintype "passive"))
    )
    (net (code "36") (name "unconnected-(U1-SYNCOUT-Pad7)") (class "Default")
      (node (ref "U1") (pin "7") (pinfunction "SYNCOUT_7") (pintype "output"))
    )
  )
)
